# CV_Control.net
KiCad netlist of a schematic drawn in Altium Designer
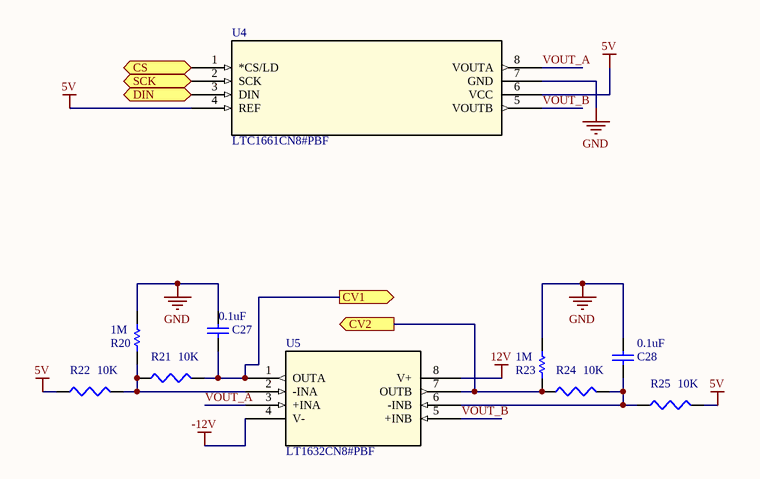
[diagram p0: CV_Control.SchDoc]

(export (version "E")
  (design (tool "Eeschema 10.0.6"))
  (components
    (comp (ref "C27")
      (value "0.1uF")
      (footprint "RAD-0.3")
      (description "Capacitor")
      (fields (field (name "Comment") "Cap") (field (name "PUBLISHER") "Altium Limited"))
      (libsource (lib "Miscellaneous Devices") (part "Cap"))
    )
    (comp (ref "C28")
      (value "0.1uF")
      (footprint "RAD-0.3")
      (description "Capacitor")
      (fields (field (name "Comment") "Cap") (field (name "PUBLISHER") "Altium Limited"))
      (libsource (lib "Miscellaneous Devices") (part "Cap"))
    )
    (comp (ref "R20")
      (value "1M")
      (footprint "AXIAL-0.3")
      (description "Resistor")
      (fields (field (name "Comment") "Res1") (field (name "PUBLISHER") "Altium Limited"))
      (libsource (lib "Miscellaneous Devices") (part "Res1"))
    )
    (comp (ref "R21")
      (value "10K")
      (footprint "J1-0603")
      (description "Resistor")
      (fields (field (name "Comment") "Res3") (field (name "PUBLISHER") "Altium Limited"))
      (libsource (lib "Miscellaneous Devices") (part "Res3"))
    )
    (comp (ref "R22")
      (value "10K")
      (footprint "J1-0603")
      (description "Resistor")
      (fields (field (name "Comment") "Res3") (field (name "PUBLISHER") "Altium Limited"))
      (libsource (lib "Miscellaneous Devices") (part "Res3"))
    )
    (comp (ref "R23")
      (value "1M")
      (footprint "AXIAL-0.3")
      (description "Resistor")
      (fields (field (name "Comment") "Res1") (field (name "PUBLISHER") "Altium Limited"))
      (libsource (lib "Miscellaneous Devices") (part "Res1"))
    )
    (comp (ref "R24")
      (value "10K")
      (footprint "J1-0603")
      (description "Resistor")
      (fields (field (name "Comment") "Res3") (field (name "PUBLISHER") "Altium Limited"))
      (libsource (lib "Miscellaneous Devices") (part "Res3"))
    )
    (comp (ref "R25")
      (value "10K")
      (footprint "J1-0603")
      (description "Resistor")
      (fields (field (name "Comment") "Res3") (field (name "PUBLISHER") "Altium Limited"))
      (libsource (lib "Miscellaneous Devices") (part "Res3"))
    )
    (comp (ref "U4")
      (value "LTC1661CN8#PBF")
      (footprint "PDIP-8_N")
      (description "Imported")
      (libsource (lib "lt1661") (part "LTC1661CN8#PBF"))
    )
    (comp (ref "U5")
      (value "LT1632CN8#PBF")
      (footprint "PDIP-8_N")
      (description "Imported")
      (fields
        (field (name "DIGIKEYPARTNUMBER") "LT1632CN8-ND")
        (field (name "COPYRIGHT") "Copyright (C) 2015 Accelerated Designs. All rights reserved")
      )
      (libsource (lib "lt1632") (part "LT1632CN8#PBF"))
    )
  )
  (nets
    (net (code "1") (name "-12V") (class "Default")
      (node (ref "U5") (pin "4") (pinfunction "V-_4") (pintype "power_in"))
    )
    (net (code "2") (name "/CS") (class "Default")
      (node (ref "U4") (pin "1") (pinfunction "*CS/LD_1") (pintype "input"))
    )
    (net (code "3") (name "/CV1") (class "Default")
      (node (ref "C27") (pin "1") (pinfunction "1_1") (pintype "passive"))
      (node (ref "R21") (pin "2") (pinfunction "2_2") (pintype "passive"))
      (node (ref "U5") (pin "1") (pinfunction "OUTA_1") (pintype "output"))
    )
    (net (code "4") (name "/CV2") (class "Default")
      (node (ref "R23") (pin "1") (pinfunction "1_1") (pintype "passive"))
      (node (ref "R24") (pin "1") (pinfunction "1_1") (pintype "passive"))
      (node (ref "U5") (pin "7") (pinfunction "OUTB_7") (pintype "output"))
    )
    (net (code "5") (name "/DIN") (class "Default")
      (node (ref "U4") (pin "3") (pinfunction "DIN_3") (pintype "input"))
    )
    (net (code "6") (name "/SCK") (class "Default")
      (node (ref "U4") (pin "2") (pinfunction "SCK_2") (pintype "input"))
    )
    (net (code "7") (name "/VOUT_A") (class "Default")
      (node (ref "U4") (pin "8") (pinfunction "VOUTA_8") (pintype "output"))
      (node (ref "U5") (pin "3") (pinfunction "+INA_3") (pintype "input"))
    )
    (net (code "8") (name "/VOUT_B") (class "Default")
      (node (ref "U4") (pin "5") (pinfunction "VOUTB_5") (pintype "output"))
      (node (ref "U5") (pin "5") (pinfunction "+INB_5") (pintype "input"))
    )
    (net (code "9") (name "5V") (class "Default")
      (node (ref "R22") (pin "1") (pinfunction "1_1") (pintype "passive"))
      (node (ref "R25") (pin "2") (pinfunction "2_2") (pintype "passive"))
      (node (ref "U4") (pin "4") (pinfunction "REF_4") (pintype "input"))
      (node (ref "U4") (pin "6") (pinfunction "VCC_6") (pintype "power_in"))
    )
    (net (code "10") (name "12V") (class "Default")
      (node (ref "U5") (pin "8") (pinfunction "V+_8") (pintype "power_in"))
    )
    (net (code "11") (name "GND") (class "Default")
      (node (ref "C27") (pin "2") (pinfunction "2_2") (pintype "passive"))
      (node (ref "C28") (pin "2") (pinfunction "2_2") (pintype "passive"))
      (node (ref "R20") (pin "2") (pinfunction "2_2") (pintype "passive"))
      (node (ref "R23") (pin "2") (pinfunction "2_2") (pintype "passive"))
      (node (ref "U4") (pin "7") (pinfunction "GND_7") (pintype "power_in"))
    )
    (net (code "12") (name "Net-(U5--INA)") (class "Default")
      (node (ref "R20") (pin "1") (pinfunction "1_1") (pintype "passive"))
      (node (ref "R21") (pin "1") (pinfunction "1_1") (pintype "passive"))
      (node (ref "R22") (pin "2") (pinfunction "2_2") (pintype "passive"))
      (node (ref "U5") (pin "2") (pinfunction "-INA_2") (pintype "input"))
    )
    (net (code "13") (name "Net-(U5--INB)") (class "Default")
      (node (ref "C28") (pin "1") (pinfunction "1_1") (pintype "passive"))
      (node (ref "R24") (pin "2") (pinfunction "2_2") (pintype "passive"))
      (node (ref "R25") (pin "1") (pinfunction "1_1") (pintype "passive"))
      (node (ref "U5") (pin "6") (pinfunction "-INB_6") (pintype "input"))
    )
  )
)
